# main.net
KiCad netlist of a schematic drawn in EAGLE
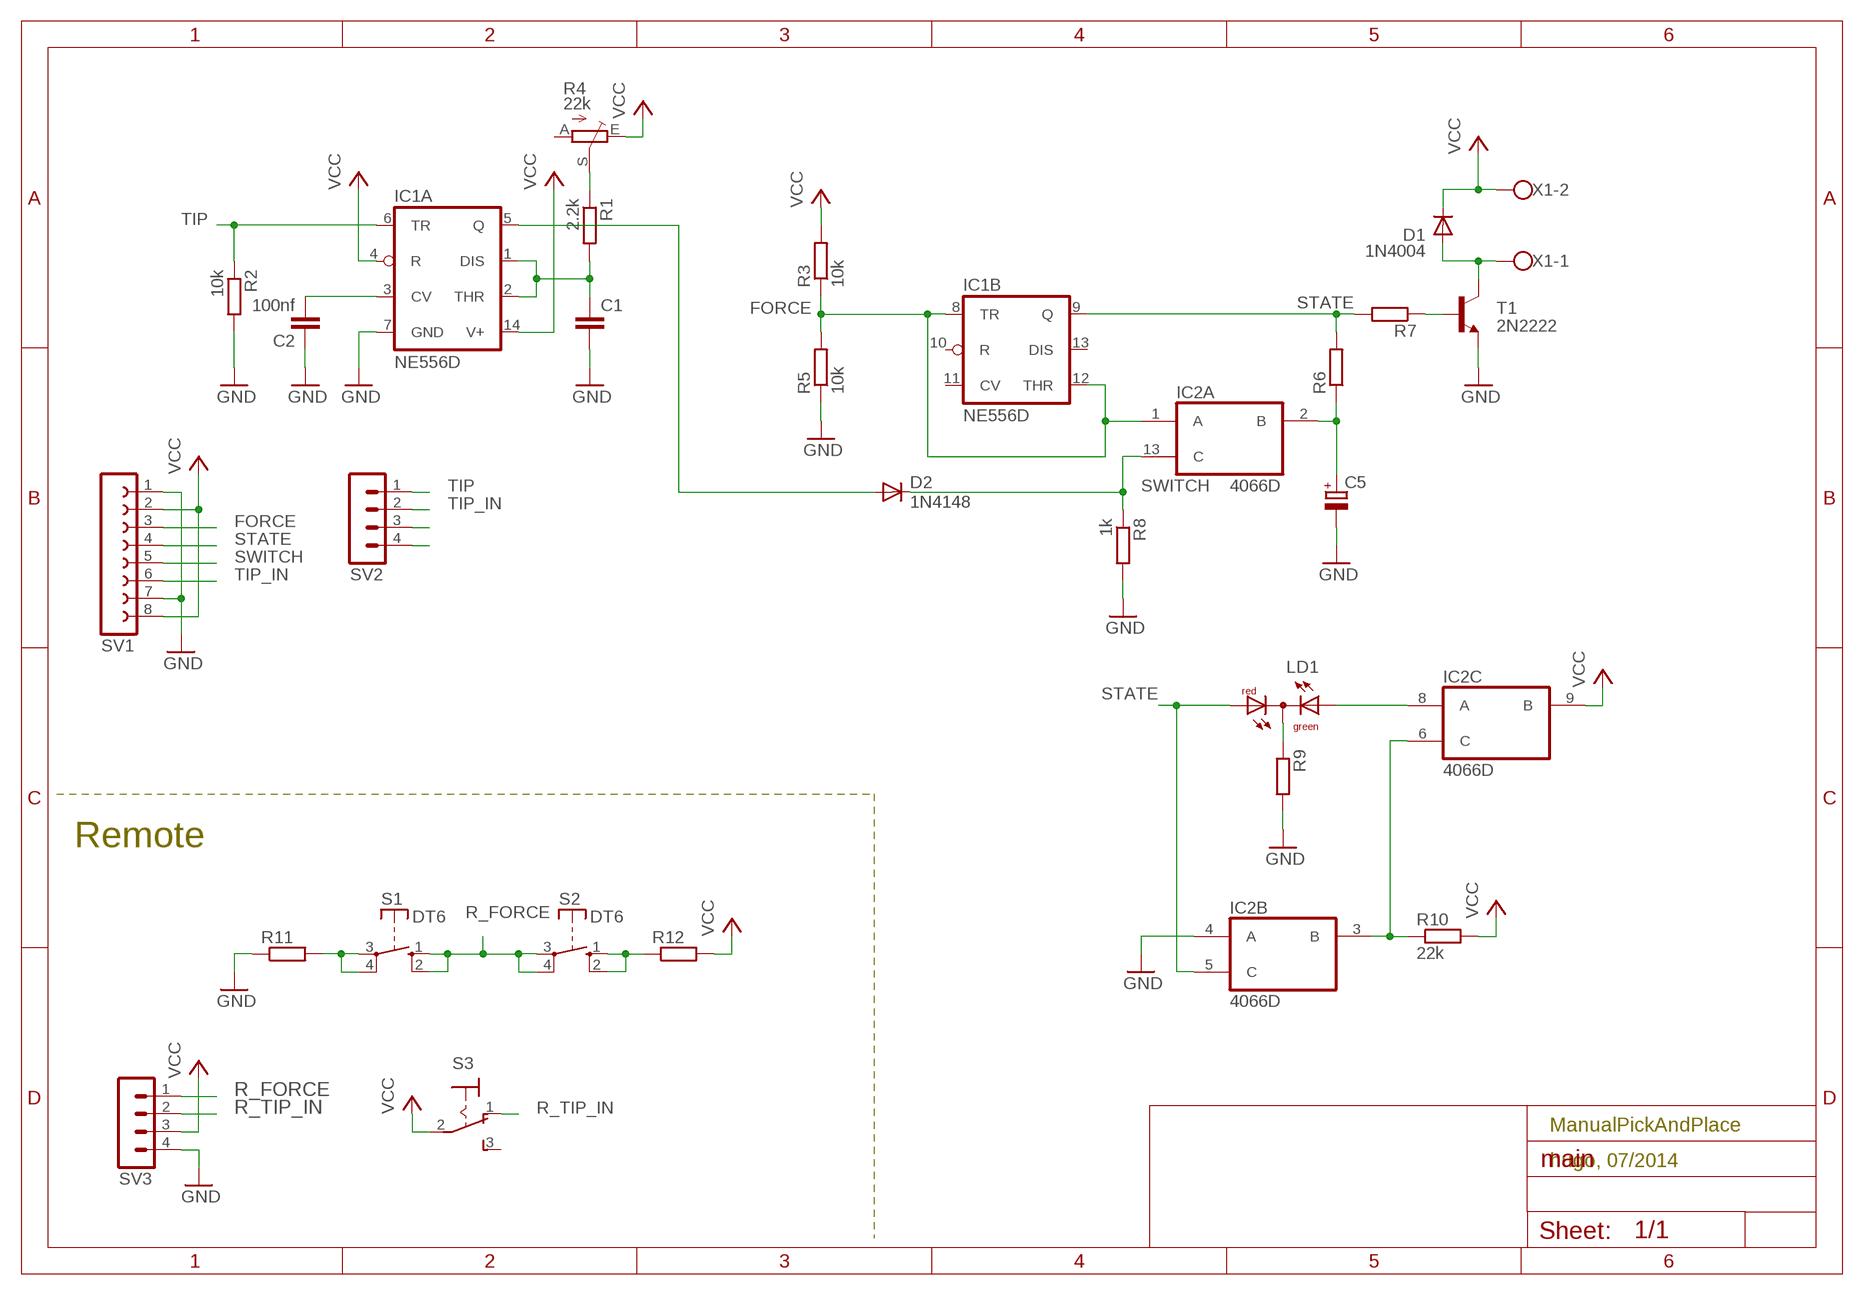
[diagram p0: schematic, sheet 1]

(export (version "E")
  (design (tool "Eeschema 10.0.6"))
  (components
    (comp (ref "C1")
      (value "C-EUC0805")
      (footprint "eagle-import:C0805")
      (libsource (lib "eagle-import") (part "C-EUC0805"))
    )
    (comp (ref "C2")
      (value "100nf")
      (footprint "eagle-import:C0805")
      (libsource (lib "eagle-import") (part "C-EUC0805"))
    )
    (comp (ref "C5")
      (value "CPOL-EUE2,5-6E")
      (footprint "eagle-import:E2,5-6E")
      (libsource (lib "eagle-import") (part "CPOL-EUE2,5-6E"))
    )
    (comp (ref "D1")
      (value "1N4004")
      (footprint "eagle-import:DO41-10")
      (libsource (lib "eagle-import") (part "1N4004"))
    )
    (comp (ref "D2")
      (value "1N4148")
      (footprint "eagle-import:DO35-7")
      (libsource (lib "eagle-import") (part "1N4148DO35-7"))
    )
    (comp (ref "IC1")
      (value "NE556D")
      (footprint "eagle-import:SO14")
      (libsource (lib "eagle-import") (part "556DNE"))
    )
    (comp (ref "IC2")
      (value "4066D")
      (footprint "eagle-import:SO14")
      (libsource (lib "eagle-import") (part "4066D"))
    )
    (comp (ref "LD1")
      (value "DUOLED-RG-C")
      (footprint "eagle-import:DUOLED-C-5MM")
      (libsource (lib "eagle-import") (part "DUOLED-RG-C"))
    )
    (comp (ref "R1")
      (value "2.2k")
      (footprint "eagle-import:R0805")
      (libsource (lib "eagle-import") (part "R-EU_R0805"))
    )
    (comp (ref "R2")
      (value "10k")
      (footprint "eagle-import:R0805")
      (libsource (lib "eagle-import") (part "R-EU_R0805"))
    )
    (comp (ref "R3")
      (value "10k")
      (footprint "eagle-import:R0805")
      (libsource (lib "eagle-import") (part "R-EU_R0805"))
    )
    (comp (ref "R4")
      (value "22k")
      (footprint "eagle-import:RJ6")
      (libsource (lib "eagle-import") (part "TRIM_EU-RJ6"))
    )
    (comp (ref "R5")
      (value "10k")
      (footprint "eagle-import:R0805")
      (libsource (lib "eagle-import") (part "R-EU_R0805"))
    )
    (comp (ref "R6")
      (value "R-EU_R0805")
      (footprint "eagle-import:R0805")
      (libsource (lib "eagle-import") (part "R-EU_R0805"))
    )
    (comp (ref "R7")
      (value "R-EU_R0805")
      (footprint "eagle-import:R0805")
      (libsource (lib "eagle-import") (part "R-EU_R0805"))
    )
    (comp (ref "R8")
      (value "1k")
      (footprint "eagle-import:R0805")
      (libsource (lib "eagle-import") (part "R-EU_R0805"))
    )
    (comp (ref "R9")
      (value "R-EU_R0805")
      (footprint "eagle-import:R0805")
      (libsource (lib "eagle-import") (part "R-EU_R0805"))
    )
    (comp (ref "R10")
      (value "22k")
      (footprint "eagle-import:R0805")
      (libsource (lib "eagle-import") (part "R-EU_R0805"))
    )
    (comp (ref "R11")
      (value "R-EU_R0805")
      (footprint "eagle-import:R0805")
      (libsource (lib "eagle-import") (part "R-EU_R0805"))
    )
    (comp (ref "R12")
      (value "R-EU_R0805")
      (footprint "eagle-import:R0805")
      (libsource (lib "eagle-import") (part "R-EU_R0805"))
    )
    (comp (ref "S1")
      (value "DT6")
      (footprint "eagle-import:DT6")
      (libsource (lib "eagle-import") (part "DT6"))
    )
    (comp (ref "S2")
      (value "DT6")
      (footprint "eagle-import:DT6")
      (libsource (lib "eagle-import") (part "DT6"))
    )
    (comp (ref "S3")
      (value "320-916")
      (footprint "eagle-import:320-916")
      (libsource (lib "eagle-import") (part "320-916"))
    )
    (comp (ref "SV1")
      (value "FE08-1")
      (footprint "eagle-import:FE08")
      (libsource (lib "eagle-import") (part "FE08-1"))
    )
    (comp (ref "SV2")
      (value "MA04-1")
      (footprint "eagle-import:MA04-1")
      (libsource (lib "eagle-import") (part "MA04-1"))
    )
    (comp (ref "SV3")
      (value "MA04-1")
      (footprint "eagle-import:MA04-1")
      (libsource (lib "eagle-import") (part "MA04-1"))
    )
    (comp (ref "T1")
      (value "2N2222")
      (footprint "eagle-import:TO18")
      (libsource (lib "eagle-import") (part "2N2222"))
    )
    (comp (ref "X1")
      (value "W237-102")
      (footprint "eagle-import:W237-102")
      (fields (field (name "MPN") "237-102"))
      (libsource (lib "eagle-import") (part "W237-102"))
    )
  )
  (nets
    (net (code "1") (name "/FORCE") (class "Default")
      (node (ref "IC1") (pin "12") (pinfunction "THR_12") (pintype "input"))
      (node (ref "IC1") (pin "8") (pinfunction "TR_8") (pintype "input"))
      (node (ref "IC2") (pin "1") (pinfunction "A_1") (pintype "tri_state"))
      (node (ref "R3") (pin "1") (pinfunction "1_1") (pintype "passive"))
      (node (ref "R5") (pin "2") (pinfunction "2_2") (pintype "passive"))
      (node (ref "SV1") (pin "3") (pinfunction "3_3") (pintype "passive"))
    )
    (net (code "2") (name "/R_FORCE") (class "Default")
      (node (ref "S1") (pin "1") (pinfunction "S_1") (pintype "passive"))
      (node (ref "S1") (pin "2") (pinfunction "S_2") (pintype "passive"))
      (node (ref "S2") (pin "3") (pinfunction "P_3") (pintype "passive"))
      (node (ref "S2") (pin "4") (pinfunction "P_4") (pintype "passive"))
      (node (ref "SV3") (pin "1") (pinfunction "1_1") (pintype "passive"))
    )
    (net (code "3") (name "/R_TIP_IN") (class "Default")
      (node (ref "S3") (pin "1") (pinfunction "O_1") (pintype "passive"))
      (node (ref "SV3") (pin "2") (pinfunction "2_2") (pintype "passive"))
    )
    (net (code "4") (name "/STATE") (class "Default")
      (node (ref "IC1") (pin "9") (pinfunction "Q_9") (pintype "output"))
      (node (ref "IC2") (pin "5") (pinfunction "C_5") (pintype "input"))
      (node (ref "LD1") (pin "AR") (pinfunction "AR_AR") (pintype "passive"))
      (node (ref "R6") (pin "2") (pinfunction "2_2") (pintype "passive"))
      (node (ref "R7") (pin "2") (pinfunction "2_2") (pintype "passive"))
      (node (ref "SV1") (pin "4") (pinfunction "4_4") (pintype "passive"))
    )
    (net (code "5") (name "/SWITCH") (class "Default")
      (node (ref "D2") (pin "C") (pinfunction "C_C") (pintype "passive"))
      (node (ref "IC2") (pin "13") (pinfunction "C_13") (pintype "input"))
      (node (ref "R8") (pin "1") (pinfunction "1_1") (pintype "passive"))
      (node (ref "SV1") (pin "5") (pinfunction "5_5") (pintype "passive"))
    )
    (net (code "6") (name "/TIP") (class "Default")
      (node (ref "IC1") (pin "6") (pinfunction "TR_6") (pintype "input"))
      (node (ref "R2") (pin "1") (pinfunction "1_1") (pintype "passive"))
      (node (ref "SV2") (pin "1") (pinfunction "1_1") (pintype "passive"))
    )
    (net (code "7") (name "/TIP_IN") (class "Default")
      (node (ref "SV1") (pin "6") (pinfunction "6_6") (pintype "passive"))
      (node (ref "SV2") (pin "2") (pinfunction "2_2") (pintype "passive"))
    )
    (net (code "8") (name "GND") (class "Default")
      (node (ref "C1") (pin "2") (pinfunction "2_2") (pintype "passive"))
      (node (ref "C2") (pin "1") (pinfunction "1_1") (pintype "passive"))
      (node (ref "C5") (pin "-") (pinfunction "-_-") (pintype "passive"))
      (node (ref "IC1") (pin "7") (pinfunction "GND_7") (pintype "power_in"))
      (node (ref "IC2") (pin "4") (pinfunction "A_4") (pintype "tri_state"))
      (node (ref "R11") (pin "1") (pinfunction "1_1") (pintype "passive"))
      (node (ref "R2") (pin "2") (pinfunction "2_2") (pintype "passive"))
      (node (ref "R5") (pin "1") (pinfunction "1_1") (pintype "passive"))
      (node (ref "R8") (pin "2") (pinfunction "2_2") (pintype "passive"))
      (node (ref "R9") (pin "2") (pinfunction "2_2") (pintype "passive"))
      (node (ref "SV1") (pin "1") (pinfunction "1_1") (pintype "passive"))
      (node (ref "SV1") (pin "7") (pinfunction "7_7") (pintype "passive"))
      (node (ref "SV3") (pin "4") (pinfunction "4_4") (pintype "passive"))
      (node (ref "T1") (pin "1") (pinfunction "E_1") (pintype "passive"))
    )
    (net (code "9") (name "Net-(IC1A-CV)") (class "Default")
      (node (ref "C2") (pin "2") (pinfunction "2_2") (pintype "passive"))
      (node (ref "IC1") (pin "3") (pinfunction "CV_3") (pintype "input"))
    )
    (net (code "10") (name "Net-(IC1A-DIS)") (class "Default")
      (node (ref "C1") (pin "1") (pinfunction "1_1") (pintype "passive"))
      (node (ref "IC1") (pin "1") (pinfunction "DIS_1") (pintype "input"))
      (node (ref "IC1") (pin "2") (pinfunction "THR_2") (pintype "input"))
      (node (ref "R1") (pin "2") (pinfunction "2_2") (pintype "passive"))
    )
    (net (code "11") (name "Net-(IC1A-Q)") (class "Default")
      (node (ref "D2") (pin "A") (pinfunction "A_A") (pintype "passive"))
      (node (ref "IC1") (pin "5") (pinfunction "Q_5") (pintype "output"))
    )
    (net (code "12") (name "Net-(IC2A-B)") (class "Default")
      (node (ref "C5") (pin "+") (pinfunction "+_+") (pintype "passive"))
      (node (ref "IC2") (pin "2") (pinfunction "B_2") (pintype "tri_state"))
      (node (ref "R6") (pin "1") (pinfunction "1_1") (pintype "passive"))
    )
    (net (code "13") (name "Net-(IC2B-B)") (class "Default")
      (node (ref "IC2") (pin "3") (pinfunction "B_3") (pintype "tri_state"))
      (node (ref "IC2") (pin "6") (pinfunction "C_6") (pintype "input"))
      (node (ref "R10") (pin "1") (pinfunction "1_1") (pintype "passive"))
    )
    (net (code "14") (name "Net-(IC2C-A)") (class "Default")
      (node (ref "IC2") (pin "8") (pinfunction "A_8") (pintype "tri_state"))
      (node (ref "LD1") (pin "AX") (pinfunction "AG_AX") (pintype "passive"))
    )
    (net (code "15") (name "Net-(LD1-PadC)") (class "Default")
      (node (ref "LD1") (pin "C") (pinfunction "C_C") (pintype "passive"))
      (node (ref "R9") (pin "1") (pinfunction "1_1") (pintype "passive"))
    )
    (net (code "16") (name "Net-(R1-Pad1)") (class "Default")
      (node (ref "R1") (pin "1") (pinfunction "1_1") (pintype "passive"))
      (node (ref "R4") (pin "S") (pinfunction "S_S") (pintype "passive"))
    )
    (net (code "17") (name "Net-(R11-Pad2)") (class "Default")
      (node (ref "R11") (pin "2") (pinfunction "2_2") (pintype "passive"))
      (node (ref "S1") (pin "3") (pinfunction "P_3") (pintype "passive"))
      (node (ref "S1") (pin "4") (pinfunction "P_4") (pintype "passive"))
    )
    (net (code "18") (name "Net-(R12-Pad1)") (class "Default")
      (node (ref "R12") (pin "1") (pinfunction "1_1") (pintype "passive"))
      (node (ref "S2") (pin "1") (pinfunction "S_1") (pintype "passive"))
      (node (ref "S2") (pin "2") (pinfunction "S_2") (pintype "passive"))
    )
    (net (code "19") (name "Net-(T1-B)") (class "Default")
      (node (ref "R7") (pin "1") (pinfunction "1_1") (pintype "passive"))
      (node (ref "T1") (pin "2") (pinfunction "B_2") (pintype "passive"))
    )
    (net (code "20") (name "Net-(T1-C)") (class "Default")
      (node (ref "D1") (pin "A") (pinfunction "A_A") (pintype "passive"))
      (node (ref "T1") (pin "3") (pinfunction "C_3") (pintype "passive"))
      (node (ref "X1") (pin "1") (pinfunction "KL_1") (pintype "passive"))
    )
    (net (code "21") (name "VCC") (class "Default")
      (node (ref "D1") (pin "C") (pinfunction "C_C") (pintype "passive"))
      (node (ref "IC1") (pin "14") (pinfunction "V+_14") (pintype "power_in"))
      (node (ref "IC1") (pin "4") (pinfunction "R_4") (pintype "input"))
      (node (ref "IC2") (pin "9") (pinfunction "B_9") (pintype "tri_state"))
      (node (ref "R10") (pin "2") (pinfunction "2_2") (pintype "passive"))
      (node (ref "R12") (pin "2") (pinfunction "2_2") (pintype "passive"))
      (node (ref "R3") (pin "2") (pinfunction "2_2") (pintype "passive"))
      (node (ref "R4") (pin "E") (pinfunction "E_E") (pintype "passive"))
      (node (ref "S3") (pin "2") (pinfunction "P_2") (pintype "passive"))
      (node (ref "SV1") (pin "2") (pinfunction "2_2") (pintype "passive"))
      (node (ref "SV1") (pin "8") (pinfunction "8_8") (pintype "passive"))
      (node (ref "SV3") (pin "3") (pinfunction "3_3") (pintype "passive"))
      (node (ref "X1") (pin "2") (pinfunction "KL_2") (pintype "passive"))
    )
    (net (code "22") (name "unconnected-(IC1B-CV-Pad11)") (class "Default")
      (node (ref "IC1") (pin "11") (pinfunction "CV_11") (pintype "input"))
    )
    (net (code "23") (name "unconnected-(IC1B-DIS-Pad13)") (class "Default")
      (node (ref "IC1") (pin "13") (pinfunction "DIS_13") (pintype "input"))
    )
    (net (code "24") (name "unconnected-(IC1B-R-Pad10)") (class "Default")
      (node (ref "IC1") (pin "10") (pinfunction "R_10") (pintype "input"))
    )
    (net (code "25") (name "unconnected-(R4-PadA)") (class "Default")
      (node (ref "R4") (pin "A") (pinfunction "A_A") (pintype "passive"))
    )
    (net (code "26") (name "unconnected-(S3-S-Pad3)") (class "Default")
      (node (ref "S3") (pin "3") (pinfunction "S_3") (pintype "passive"))
    )
    (net (code "27") (name "unconnected-(SV2-Pad3)") (class "Default")
      (node (ref "SV2") (pin "3") (pinfunction "3_3") (pintype "passive"))
    )
    (net (code "28") (name "unconnected-(SV2-Pad4)") (class "Default")
      (node (ref "SV2") (pin "4") (pinfunction "4_4") (pintype "passive"))
    )
  )
)
